# Keyglove_Kit_v0_3.net
KiCad netlist of a schematic drawn in EAGLE
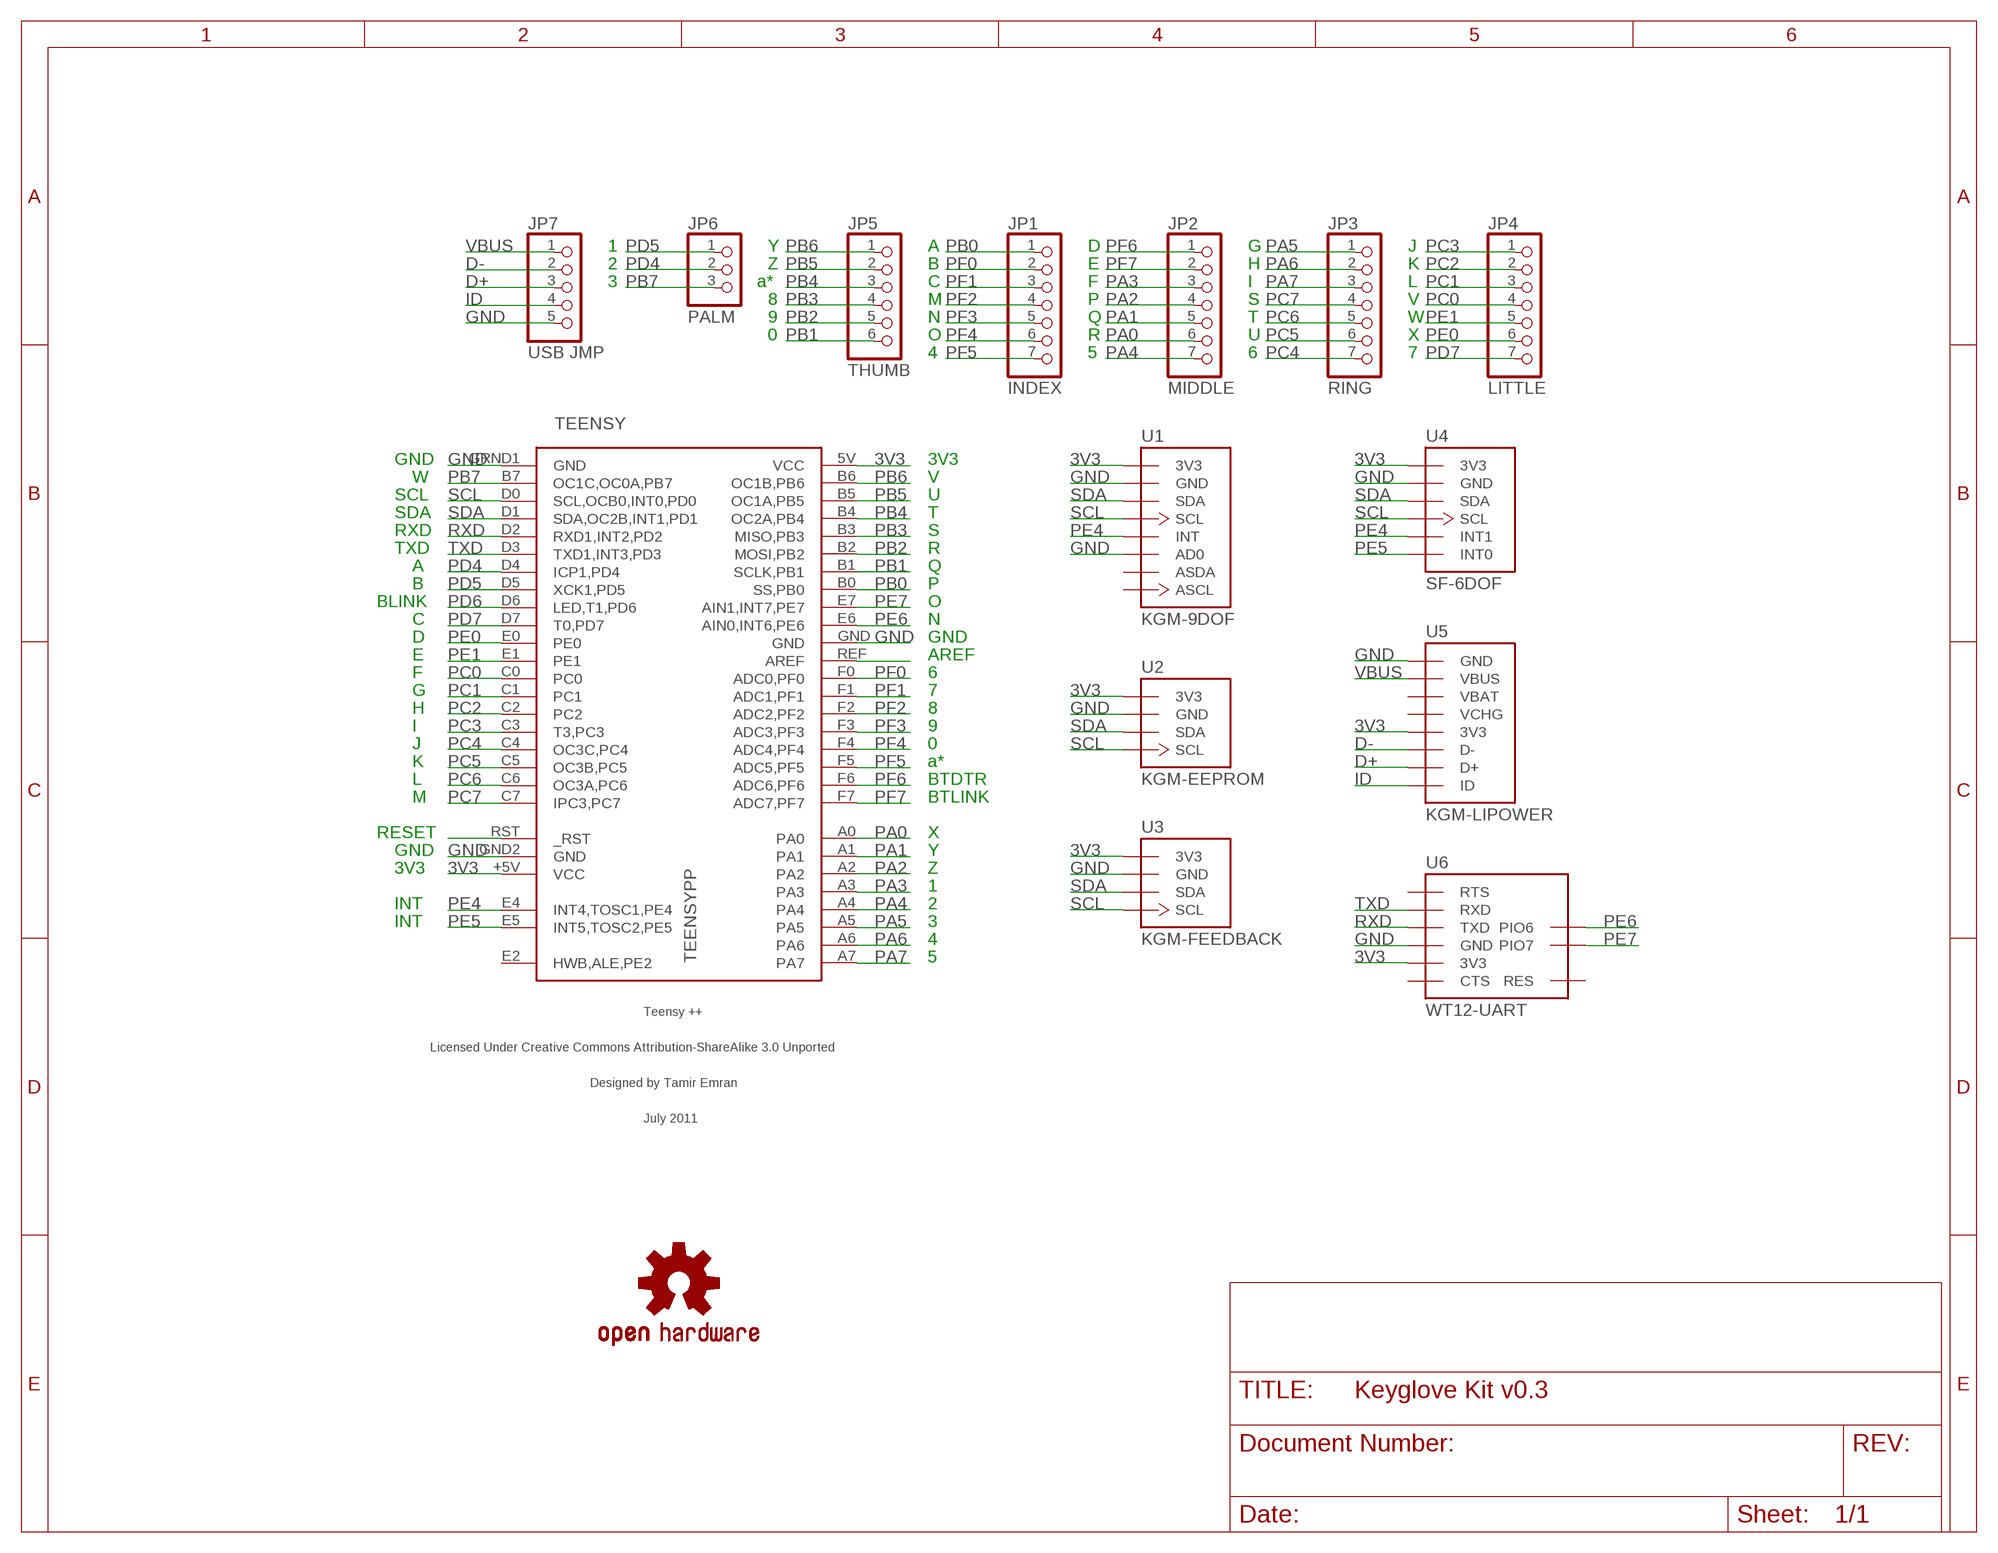
[diagram p0: schematic, sheet 1]

(export (version "E")
  (design (tool "Eeschema 10.0.6"))
  (components
    (comp (ref "JP1")
      (value "INDEX")
      (footprint "eagle-import:1X07")
      (libsource (lib "eagle-import") (part "PINHD-1X7"))
    )
    (comp (ref "JP2")
      (value "MIDDLE")
      (footprint "eagle-import:1X07")
      (libsource (lib "eagle-import") (part "PINHD-1X7"))
    )
    (comp (ref "JP3")
      (value "RING")
      (footprint "eagle-import:1X07")
      (libsource (lib "eagle-import") (part "PINHD-1X7"))
    )
    (comp (ref "JP4")
      (value "LITTLE")
      (footprint "eagle-import:1X07")
      (libsource (lib "eagle-import") (part "PINHD-1X7"))
    )
    (comp (ref "JP5")
      (value "THUMB")
      (footprint "eagle-import:1X06")
      (libsource (lib "eagle-import") (part "PINHD-1X6"))
    )
    (comp (ref "JP6")
      (value "PALM")
      (footprint "eagle-import:1X03")
      (libsource (lib "eagle-import") (part "PINHD-1X3"))
    )
    (comp (ref "JP7")
      (value "USB JMP")
      (footprint "eagle-import:1X05")
      (libsource (lib "eagle-import") (part "PINHD-1X5"))
    )
    (comp (ref "TEENSY")
      (value "TEENSYPP")
      (footprint "eagle-import:TEENSYPP")
      (libsource (lib "eagle-import") (part "TEENSYPP"))
    )
    (comp (ref "U$1")
      (value "OSHW-LOGOM")
      (footprint "eagle-import:OSHW-LOGO-M")
      (libsource (lib "eagle-import") (part "OSHW-LOGOM"))
    )
    (comp (ref "U1")
      (value "KGM-9DOF")
      (footprint "eagle-import:KGM-9DOF")
      (libsource (lib "eagle-import") (part "KGM-9DOF"))
    )
    (comp (ref "U2")
      (value "KGM-EEPROM")
      (footprint "eagle-import:KGM-EEPROM")
      (libsource (lib "eagle-import") (part "KGM-EEPROM"))
    )
    (comp (ref "U3")
      (value "KGM-FEEDBACK")
      (footprint "eagle-import:KGM-FEEDBACK")
      (libsource (lib "eagle-import") (part "KGM-FEEDBACK"))
    )
    (comp (ref "U4")
      (value "SF-6DOF")
      (footprint "eagle-import:SF-6DOF")
      (libsource (lib "eagle-import") (part "SF-6DOF"))
    )
    (comp (ref "U5")
      (value "KGM-LIPOWER")
      (footprint "eagle-import:KGM-LIPOWER")
      (libsource (lib "eagle-import") (part "KGM-LIPOWER"))
    )
    (comp (ref "U6")
      (value "WT12-UART")
      (footprint "eagle-import:WT12-UART")
      (libsource (lib "eagle-import") (part "WT12-UART"))
    )
  )
  (nets
    (net (code "1") (name "/3V3") (class "Default")
      (node (ref "TEENSY") (pin "+5V") (pinfunction "VCC_+5V") (pintype "power_in"))
      (node (ref "TEENSY") (pin "5V") (pinfunction "VCC_5V") (pintype "power_in"))
      (node (ref "U1") (pin "3V3") (pinfunction "3V3_3V3") (pintype "power_in"))
      (node (ref "U2") (pin "3V3") (pinfunction "3V3_3V3") (pintype "power_in"))
      (node (ref "U3") (pin "3V3") (pinfunction "3V3_3V3") (pintype "power_in"))
      (node (ref "U4") (pin "3V3") (pinfunction "3V3_3V3") (pintype "power_in"))
      (node (ref "U5") (pin "3V3") (pinfunction "3V3_3V3") (pintype "power_in"))
      (node (ref "U6") (pin "3V3") (pinfunction "3V3_3V3") (pintype "power_in"))
    )
    (net (code "2") (name "/D+") (class "Default")
      (node (ref "JP7") (pin "3") (pinfunction "3_3") (pintype "passive"))
      (node (ref "U5") (pin "D+") (pinfunction "D+_D+") (pintype "bidirectional"))
    )
    (net (code "3") (name "/D-") (class "Default")
      (node (ref "JP7") (pin "2") (pinfunction "2_2") (pintype "passive"))
      (node (ref "U5") (pin "D-") (pinfunction "D-_D-") (pintype "bidirectional"))
    )
    (net (code "4") (name "/GND") (class "Default")
      (node (ref "JP7") (pin "5") (pinfunction "5_5") (pintype "passive"))
      (node (ref "TEENSY") (pin "GND") (pinfunction "GND_GND") (pintype "power_in"))
      (node (ref "TEENSY") (pin "GND2") (pinfunction "GND_GND2") (pintype "power_in"))
      (node (ref "TEENSY") (pin "GRND1") (pinfunction "GND_GRND1") (pintype "power_in"))
      (node (ref "U1") (pin "AD0") (pinfunction "AD0_AD0") (pintype "input"))
      (node (ref "U1") (pin "GND") (pinfunction "GND_GND") (pintype "power_in"))
      (node (ref "U2") (pin "GND") (pinfunction "GND_GND") (pintype "power_in"))
      (node (ref "U3") (pin "GND") (pinfunction "GND_GND") (pintype "power_in"))
      (node (ref "U4") (pin "GND") (pinfunction "GND_GND") (pintype "power_in"))
      (node (ref "U5") (pin "GND") (pinfunction "GND_GND") (pintype "power_in"))
      (node (ref "U6") (pin "GND") (pinfunction "GND_GND") (pintype "power_in"))
    )
    (net (code "5") (name "/ID") (class "Default")
      (node (ref "JP7") (pin "4") (pinfunction "4_4") (pintype "passive"))
      (node (ref "U5") (pin "ID") (pinfunction "ID_ID") (pintype "bidirectional"))
    )
    (net (code "6") (name "/PA0") (class "Default")
      (node (ref "JP2") (pin "6") (pinfunction "6_6") (pintype "passive"))
      (node (ref "TEENSY") (pin "A0") (pinfunction "PA0_A0") (pintype "bidirectional"))
    )
    (net (code "7") (name "/PA1") (class "Default")
      (node (ref "JP2") (pin "5") (pinfunction "5_5") (pintype "passive"))
      (node (ref "TEENSY") (pin "A1") (pinfunction "PA1_A1") (pintype "bidirectional"))
    )
    (net (code "8") (name "/PA2") (class "Default")
      (node (ref "JP2") (pin "4") (pinfunction "4_4") (pintype "passive"))
      (node (ref "TEENSY") (pin "A2") (pinfunction "PA2_A2") (pintype "bidirectional"))
    )
    (net (code "9") (name "/PA3") (class "Default")
      (node (ref "JP2") (pin "3") (pinfunction "3_3") (pintype "passive"))
      (node (ref "TEENSY") (pin "A3") (pinfunction "PA3_A3") (pintype "bidirectional"))
    )
    (net (code "10") (name "/PA4") (class "Default")
      (node (ref "JP2") (pin "7") (pinfunction "7_7") (pintype "passive"))
      (node (ref "TEENSY") (pin "A4") (pinfunction "PA4_A4") (pintype "bidirectional"))
    )
    (net (code "11") (name "/PA5") (class "Default")
      (node (ref "JP3") (pin "1") (pinfunction "1_1") (pintype "passive"))
      (node (ref "TEENSY") (pin "A5") (pinfunction "PA5_A5") (pintype "bidirectional"))
    )
    (net (code "12") (name "/PA6") (class "Default")
      (node (ref "JP3") (pin "2") (pinfunction "2_2") (pintype "passive"))
      (node (ref "TEENSY") (pin "A6") (pinfunction "PA6_A6") (pintype "bidirectional"))
    )
    (net (code "13") (name "/PA7") (class "Default")
      (node (ref "JP3") (pin "3") (pinfunction "3_3") (pintype "passive"))
      (node (ref "TEENSY") (pin "A7") (pinfunction "PA7_A7") (pintype "bidirectional"))
    )
    (net (code "14") (name "/PB0") (class "Default")
      (node (ref "JP1") (pin "1") (pinfunction "1_1") (pintype "passive"))
      (node (ref "TEENSY") (pin "B0") (pinfunction "SS,PB0_B0") (pintype "bidirectional"))
    )
    (net (code "15") (name "/PB1") (class "Default")
      (node (ref "JP5") (pin "6") (pinfunction "6_6") (pintype "passive"))
      (node (ref "TEENSY") (pin "B1") (pinfunction "SCLK,PB1_B1") (pintype "bidirectional"))
    )
    (net (code "16") (name "/PB2") (class "Default")
      (node (ref "JP5") (pin "5") (pinfunction "5_5") (pintype "passive"))
      (node (ref "TEENSY") (pin "B2") (pinfunction "MOSI,PB2_B2") (pintype "bidirectional"))
    )
    (net (code "17") (name "/PB3") (class "Default")
      (node (ref "JP5") (pin "4") (pinfunction "4_4") (pintype "passive"))
      (node (ref "TEENSY") (pin "B3") (pinfunction "MISO,PB3_B3") (pintype "bidirectional"))
    )
    (net (code "18") (name "/PB4") (class "Default")
      (node (ref "JP5") (pin "3") (pinfunction "3_3") (pintype "passive"))
      (node (ref "TEENSY") (pin "B4") (pinfunction "OC2A,PB4_B4") (pintype "bidirectional"))
    )
    (net (code "19") (name "/PB5") (class "Default")
      (node (ref "JP5") (pin "2") (pinfunction "2_2") (pintype "passive"))
      (node (ref "TEENSY") (pin "B5") (pinfunction "OC1A,PB5_B5") (pintype "bidirectional"))
    )
    (net (code "20") (name "/PB6") (class "Default")
      (node (ref "JP5") (pin "1") (pinfunction "1_1") (pintype "passive"))
      (node (ref "TEENSY") (pin "B6") (pinfunction "OC1B,PB6_B6") (pintype "bidirectional"))
    )
    (net (code "21") (name "/PB7") (class "Default")
      (node (ref "JP6") (pin "3") (pinfunction "3_3") (pintype "passive"))
      (node (ref "TEENSY") (pin "B7") (pinfunction "OC1C,OC0A,PB7_B7") (pintype "bidirectional"))
    )
    (net (code "22") (name "/PC0") (class "Default")
      (node (ref "JP4") (pin "4") (pinfunction "4_4") (pintype "passive"))
      (node (ref "TEENSY") (pin "C0") (pinfunction "PC0_C0") (pintype "bidirectional"))
    )
    (net (code "23") (name "/PC1") (class "Default")
      (node (ref "JP4") (pin "3") (pinfunction "3_3") (pintype "passive"))
      (node (ref "TEENSY") (pin "C1") (pinfunction "PC1_C1") (pintype "bidirectional"))
    )
    (net (code "24") (name "/PC2") (class "Default")
      (node (ref "JP4") (pin "2") (pinfunction "2_2") (pintype "passive"))
      (node (ref "TEENSY") (pin "C2") (pinfunction "PC2_C2") (pintype "bidirectional"))
    )
    (net (code "25") (name "/PC3") (class "Default")
      (node (ref "JP4") (pin "1") (pinfunction "1_1") (pintype "passive"))
      (node (ref "TEENSY") (pin "C3") (pinfunction "T3,PC3_C3") (pintype "bidirectional"))
    )
    (net (code "26") (name "/PC4") (class "Default")
      (node (ref "JP3") (pin "7") (pinfunction "7_7") (pintype "passive"))
      (node (ref "TEENSY") (pin "C4") (pinfunction "OC3C,PC4_C4") (pintype "bidirectional"))
    )
    (net (code "27") (name "/PC5") (class "Default")
      (node (ref "JP3") (pin "6") (pinfunction "6_6") (pintype "passive"))
      (node (ref "TEENSY") (pin "C5") (pinfunction "OC3B,PC5_C5") (pintype "bidirectional"))
    )
    (net (code "28") (name "/PC6") (class "Default")
      (node (ref "JP3") (pin "5") (pinfunction "5_5") (pintype "passive"))
      (node (ref "TEENSY") (pin "C6") (pinfunction "OC3A,PC6_C6") (pintype "bidirectional"))
    )
    (net (code "29") (name "/PC7") (class "Default")
      (node (ref "JP3") (pin "4") (pinfunction "4_4") (pintype "passive"))
      (node (ref "TEENSY") (pin "C7") (pinfunction "IPC3,PC7_C7") (pintype "bidirectional"))
    )
    (net (code "30") (name "/PD4") (class "Default")
      (node (ref "JP6") (pin "2") (pinfunction "2_2") (pintype "passive"))
      (node (ref "TEENSY") (pin "D4") (pinfunction "ICP1,PD4_D4") (pintype "bidirectional"))
    )
    (net (code "31") (name "/PD5") (class "Default")
      (node (ref "JP6") (pin "1") (pinfunction "1_1") (pintype "passive"))
      (node (ref "TEENSY") (pin "D5") (pinfunction "XCK1,PD5_D5") (pintype "bidirectional"))
    )
    (net (code "32") (name "/PD6") (class "Default")
      (node (ref "TEENSY") (pin "D6") (pinfunction "LED,T1,PD6_D6") (pintype "bidirectional"))
    )
    (net (code "33") (name "/PD7") (class "Default")
      (node (ref "JP4") (pin "7") (pinfunction "7_7") (pintype "passive"))
      (node (ref "TEENSY") (pin "D7") (pinfunction "T0,PD7_D7") (pintype "bidirectional"))
    )
    (net (code "34") (name "/PE0") (class "Default")
      (node (ref "JP4") (pin "6") (pinfunction "6_6") (pintype "passive"))
      (node (ref "TEENSY") (pin "E0") (pinfunction "PE0_E0") (pintype "bidirectional"))
    )
    (net (code "35") (name "/PE1") (class "Default")
      (node (ref "JP4") (pin "5") (pinfunction "5_5") (pintype "passive"))
      (node (ref "TEENSY") (pin "E1") (pinfunction "PE1_E1") (pintype "bidirectional"))
    )
    (net (code "36") (name "/PE4") (class "Default")
      (node (ref "TEENSY") (pin "E4") (pinfunction "INT4,TOSC1,PE4_E4") (pintype "bidirectional"))
      (node (ref "U1") (pin "INT") (pinfunction "INT_INT") (pintype "output"))
      (node (ref "U4") (pin "INT1") (pinfunction "INT1_INT1") (pintype "output"))
    )
    (net (code "37") (name "/PE5") (class "Default")
      (node (ref "TEENSY") (pin "E5") (pinfunction "INT5,TOSC2,PE5_E5") (pintype "bidirectional"))
      (node (ref "U4") (pin "INT0") (pinfunction "INT0_INT0") (pintype "output"))
    )
    (net (code "38") (name "/PE6") (class "Default")
      (node (ref "TEENSY") (pin "E6") (pinfunction "AIN0,INT6,PE6_E6") (pintype "bidirectional"))
      (node (ref "U6") (pin "PIO6") (pinfunction "PIO6_PIO6") (pintype "bidirectional"))
    )
    (net (code "39") (name "/PE7") (class "Default")
      (node (ref "TEENSY") (pin "E7") (pinfunction "AIN1,INT7,PE7_E7") (pintype "bidirectional"))
      (node (ref "U6") (pin "PIO7") (pinfunction "PIO7_PIO7") (pintype "bidirectional"))
    )
    (net (code "40") (name "/PF0") (class "Default")
      (node (ref "JP1") (pin "2") (pinfunction "2_2") (pintype "passive"))
      (node (ref "TEENSY") (pin "F0") (pinfunction "ADC0,PF0_F0") (pintype "bidirectional"))
    )
    (net (code "41") (name "/PF1") (class "Default")
      (node (ref "JP1") (pin "3") (pinfunction "3_3") (pintype "passive"))
      (node (ref "TEENSY") (pin "F1") (pinfunction "ADC1,PF1_F1") (pintype "bidirectional"))
    )
    (net (code "42") (name "/PF2") (class "Default")
      (node (ref "JP1") (pin "4") (pinfunction "4_4") (pintype "passive"))
      (node (ref "TEENSY") (pin "F2") (pinfunction "ADC2,PF2_F2") (pintype "bidirectional"))
    )
    (net (code "43") (name "/PF3") (class "Default")
      (node (ref "JP1") (pin "5") (pinfunction "5_5") (pintype "passive"))
      (node (ref "TEENSY") (pin "F3") (pinfunction "ADC3,PF3_F3") (pintype "bidirectional"))
    )
    (net (code "44") (name "/PF4") (class "Default")
      (node (ref "JP1") (pin "6") (pinfunction "6_6") (pintype "passive"))
      (node (ref "TEENSY") (pin "F4") (pinfunction "ADC4,PF4_F4") (pintype "bidirectional"))
    )
    (net (code "45") (name "/PF5") (class "Default")
      (node (ref "JP1") (pin "7") (pinfunction "7_7") (pintype "passive"))
      (node (ref "TEENSY") (pin "F5") (pinfunction "ADC5,PF5_F5") (pintype "bidirectional"))
    )
    (net (code "46") (name "/PF6") (class "Default")
      (node (ref "JP2") (pin "1") (pinfunction "1_1") (pintype "passive"))
      (node (ref "TEENSY") (pin "F6") (pinfunction "ADC6,PF6_F6") (pintype "bidirectional"))
    )
    (net (code "47") (name "/PF7") (class "Default")
      (node (ref "JP2") (pin "2") (pinfunction "2_2") (pintype "passive"))
      (node (ref "TEENSY") (pin "F7") (pinfunction "ADC7,PF7_F7") (pintype "bidirectional"))
    )
    (net (code "48") (name "/RXD") (class "Default")
      (node (ref "TEENSY") (pin "D2") (pinfunction "RXD1,INT2,PD2_D2") (pintype "bidirectional"))
      (node (ref "U6") (pin "TXD") (pinfunction "TXD_TXD") (pintype "output"))
    )
    (net (code "49") (name "/SCL") (class "Default")
      (node (ref "TEENSY") (pin "D0") (pinfunction "SCL,OCB0,INT0,PD0_D0") (pintype "bidirectional"))
      (node (ref "U1") (pin "SCL") (pinfunction "SCL_SCL") (pintype "bidirectional"))
      (node (ref "U2") (pin "SCL") (pinfunction "SCL_SCL") (pintype "bidirectional"))
      (node (ref "U3") (pin "SCL") (pinfunction "SCL_SCL") (pintype "bidirectional"))
      (node (ref "U4") (pin "SCL") (pinfunction "SCL_SCL") (pintype "bidirectional"))
    )
    (net (code "50") (name "/SDA") (class "Default")
      (node (ref "TEENSY") (pin "D1") (pinfunction "SDA,OC2B,INT1,PD1_D1") (pintype "bidirectional"))
      (node (ref "U1") (pin "SDA") (pinfunction "SDA_SDA") (pintype "bidirectional"))
      (node (ref "U2") (pin "SDA") (pinfunction "SDA_SDA") (pintype "bidirectional"))
      (node (ref "U3") (pin "SDA") (pinfunction "SDA_SDA") (pintype "bidirectional"))
      (node (ref "U4") (pin "SDA") (pinfunction "SDA_SDA") (pintype "bidirectional"))
    )
    (net (code "51") (name "/TXD") (class "Default")
      (node (ref "TEENSY") (pin "D3") (pinfunction "TXD1,INT3,PD3_D3") (pintype "bidirectional"))
      (node (ref "U6") (pin "RXD") (pinfunction "RXD_RXD") (pintype "input"))
    )
    (net (code "52") (name "/VBAT") (class "Default")
      (node (ref "U5") (pin "VBAT") (pinfunction "VBAT_VBAT") (pintype "power_in"))
    )
    (net (code "53") (name "/VBUS") (class "Default")
      (node (ref "JP7") (pin "1") (pinfunction "1_1") (pintype "passive"))
      (node (ref "U5") (pin "VBUS") (pinfunction "VBUS_VBUS") (pintype "power_in"))
    )
    (net (code "54") (name "/VCHG") (class "Default")
      (node (ref "U5") (pin "VCHG") (pinfunction "VCHG_VCHG") (pintype "power_in"))
    )
    (net (code "55") (name "unconnected-(TEENSY-AREF-PadREF)") (class "Default")
      (node (ref "TEENSY") (pin "REF") (pinfunction "AREF_REF") (pintype "input"))
    )
    (net (code "56") (name "unconnected-(TEENSY-HWB,ALE,PE2-PadE2)") (class "Default")
      (node (ref "TEENSY") (pin "E2") (pinfunction "HWB,ALE,PE2_E2") (pintype "bidirectional"))
    )
    (net (code "57") (name "unconnected-(TEENSY-_RST-PadRST)") (class "Default")
      (node (ref "TEENSY") (pin "RST") (pinfunction "_RST_RST") (pintype "input"))
    )
    (net (code "58") (name "unconnected-(U1-PadASCL)") (class "Default")
      (node (ref "U1") (pin "ASCL") (pinfunction "ASCL_ASCL") (pintype "bidirectional"))
    )
    (net (code "59") (name "unconnected-(U1-PadASDA)") (class "Default")
      (node (ref "U1") (pin "ASDA") (pinfunction "ASDA_ASDA") (pintype "bidirectional"))
    )
    (net (code "60") (name "unconnected-(U6-PadCTS)") (class "Default")
      (node (ref "U6") (pin "CTS") (pinfunction "CTS_CTS") (pintype "input"))
    )
    (net (code "61") (name "unconnected-(U6-PadRTS)") (class "Default")
      (node (ref "U6") (pin "RTS") (pinfunction "RTS_RTS") (pintype "output"))
    )
    (net (code "62") (name "unconnected-(U6-RES-PadRESET)") (class "Default")
      (node (ref "U6") (pin "RESET") (pinfunction "RES_RESET") (pintype "input"))
    )
  )
)
